# PCB.net
KiCad netlist of a schematic drawn in EAGLE
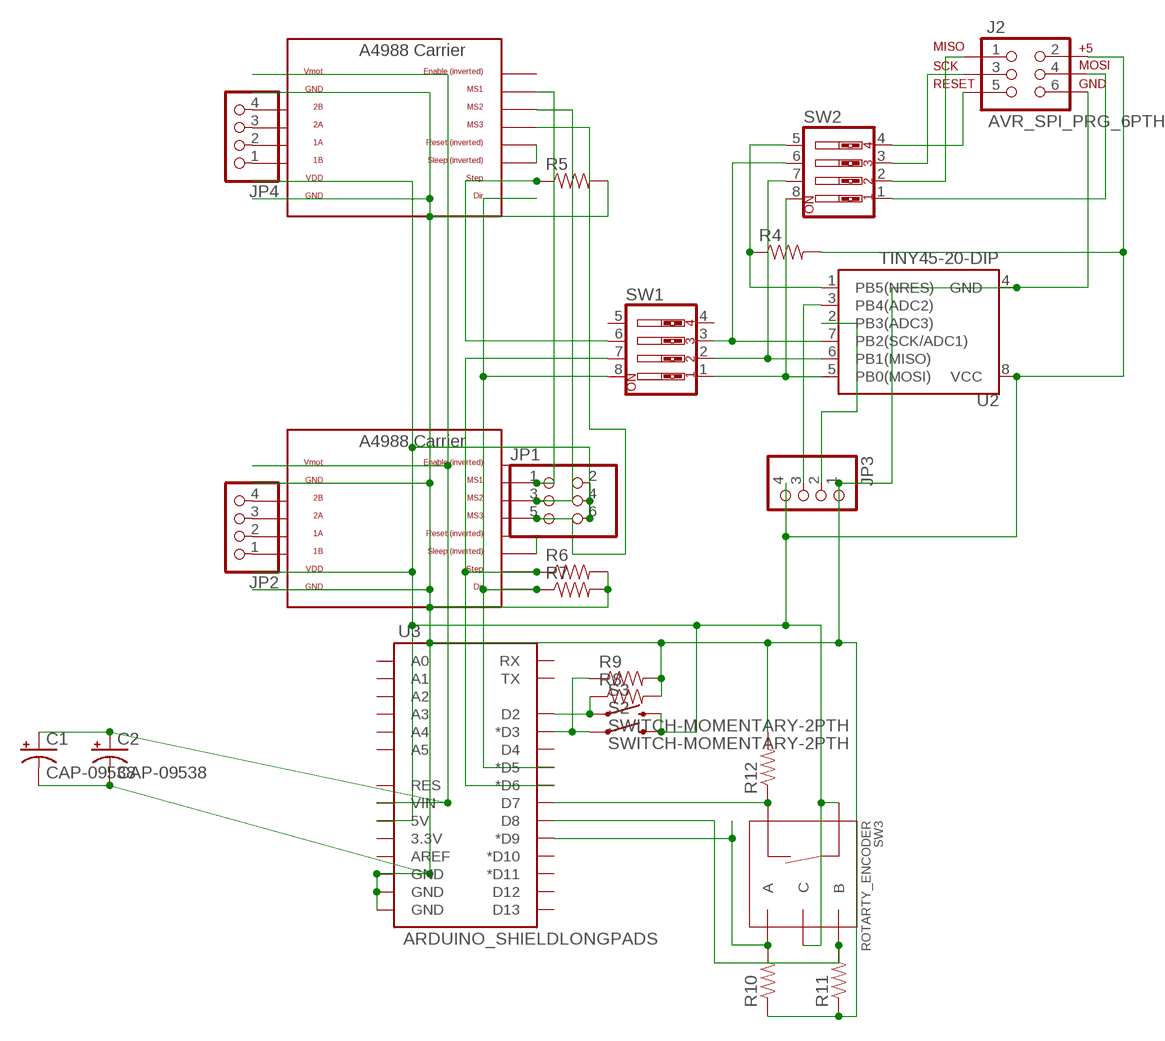
[diagram p0: schematic, sheet 1]

(export (version "E")
  (design (tool "Eeschema 10.0.6"))
  (components
    (comp (ref "C1")
      (value "CAP-09538")
      (footprint "eagle-import:CPOL-RADIAL-1000UF-25V")
      (libsource (lib "eagle-import") (part "1000UF-25V(PTH)"))
    )
    (comp (ref "C2")
      (value "CAP-09538")
      (footprint "eagle-import:CPOL-RADIAL-1000UF-25V")
      (libsource (lib "eagle-import") (part "1000UF-25V(PTH)"))
    )
    (comp (ref "J2")
      (value "AVR_SPI_PRG_6PTH")
      (footprint "eagle-import:2X3")
      (libsource (lib "eagle-import") (part "AVR_SPI_PRG_6PTH"))
    )
    (comp (ref "JP1")
      (value "PINHD-2X3")
      (footprint "eagle-import:2X03")
      (libsource (lib "eagle-import") (part "PINHD-2X3"))
    )
    (comp (ref "JP2")
      (value "PINHD-1X4")
      (footprint "eagle-import:1X04")
      (libsource (lib "eagle-import") (part "PINHD-1X4"))
    )
    (comp (ref "JP3")
      (value "PINHD-1X4")
      (footprint "eagle-import:1X04")
      (libsource (lib "eagle-import") (part "PINHD-1X4"))
    )
    (comp (ref "JP4")
      (value "PINHD-1X4")
      (footprint "eagle-import:1X04")
      (libsource (lib "eagle-import") (part "PINHD-1X4"))
    )
    (comp (ref "R4")
      (value "RESISTOR1206")
      (footprint "eagle-import:1206")
      (libsource (lib "eagle-import") (part "RESISTOR1206"))
    )
    (comp (ref "R5")
      (value "RESISTOR1206")
      (footprint "eagle-import:1206")
      (libsource (lib "eagle-import") (part "RESISTOR1206"))
    )
    (comp (ref "R6")
      (value "RESISTOR1206")
      (footprint "eagle-import:1206")
      (libsource (lib "eagle-import") (part "RESISTOR1206"))
    )
    (comp (ref "R7")
      (value "RESISTOR1206")
      (footprint "eagle-import:1206")
      (libsource (lib "eagle-import") (part "RESISTOR1206"))
    )
    (comp (ref "R8")
      (value "RESISTOR1206")
      (footprint "eagle-import:1206")
      (libsource (lib "eagle-import") (part "RESISTOR1206"))
    )
    (comp (ref "R9")
      (value "RESISTOR1206")
      (footprint "eagle-import:1206")
      (libsource (lib "eagle-import") (part "RESISTOR1206"))
    )
    (comp (ref "R10")
      (value "RESISTOR1206")
      (footprint "eagle-import:1206")
      (libsource (lib "eagle-import") (part "RESISTOR1206"))
    )
    (comp (ref "R11")
      (value "RESISTOR1206")
      (footprint "eagle-import:1206")
      (libsource (lib "eagle-import") (part "RESISTOR1206"))
    )
    (comp (ref "R12")
      (value "RESISTOR1206")
      (footprint "eagle-import:1206")
      (libsource (lib "eagle-import") (part "RESISTOR1206"))
    )
    (comp (ref "S2")
      (value "SWITCH-MOMENTARY-2PTH")
      (footprint "eagle-import:TACTILE-PTH")
      (libsource (lib "eagle-import") (part "SWITCH-MOMENTARY-2PTH"))
    )
    (comp (ref "S3")
      (value "SWITCH-MOMENTARY-2PTH")
      (footprint "eagle-import:TACTILE-PTH")
      (libsource (lib "eagle-import") (part "SWITCH-MOMENTARY-2PTH"))
    )
    (comp (ref "SW1")
      (value "SW_DIP-4")
      (footprint "eagle-import:EDG-04")
      (libsource (lib "eagle-import") (part "SW_DIP-4"))
    )
    (comp (ref "SW2")
      (value "SW_DIP-4")
      (footprint "eagle-import:EDG-04")
      (libsource (lib "eagle-import") (part "SW_DIP-4"))
    )
    (comp (ref "SW3")
      (value "ROTARTY_ENCODER")
      (footprint "eagle-import:ROTARY_ENC_PLAIN")
      (libsource (lib "eagle-import") (part "ROTARTY_ENCODER"))
    )
    (comp (ref "U$3")
      (value "A4988BREAKOUT")
      (footprint "eagle-import:A4988BREAKOUT")
      (libsource (lib "eagle-import") (part "A4988BREAKOUT"))
    )
    (comp (ref "U$4")
      (value "A4988BREAKOUT")
      (footprint "eagle-import:A4988BREAKOUT")
      (libsource (lib "eagle-import") (part "A4988BREAKOUT"))
    )
    (comp (ref "U2")
      (value "TINY45-20-DIP")
      (footprint "eagle-import:DIP08")
      (libsource (lib "eagle-import") (part "ATTINY45TINY45-20-DIP"))
    )
    (comp (ref "U3")
      (value "ARDUINO_SHIELDLONGPADS")
      (footprint "eagle-import:DUEMILANOVE_SHIELD_LONGPADS")
      (libsource (lib "eagle-import") (part "ARDUINO_SHIELDLONGPADS"))
    )
  )
  (nets
    (net (code "1") (name "Net-(C1-Pad+)") (class "Default")
      (node (ref "C1") (pin "+") (pinfunction "+_+") (pintype "passive"))
      (node (ref "C2") (pin "+") (pinfunction "+_+") (pintype "passive"))
      (node (ref "U$3") (pin "VMOT") (pinfunction "VMOT_VMOT") (pintype "power_in"))
      (node (ref "U$4") (pin "VMOT") (pinfunction "VMOT_VMOT") (pintype "power_in"))
      (node (ref "U3") (pin "VIN") (pinfunction "VIN_VIN") (pintype "bidirectional"))
    )
    (net (code "2") (name "Net-(J2-Pad1)") (class "Default")
      (node (ref "J2") (pin "1") (pinfunction "1_1") (pintype "passive"))
      (node (ref "SW2") (pin "2") (pinfunction "2_2") (pintype "passive"))
    )
    (net (code "3") (name "Net-(J2-Pad3)") (class "Default")
      (node (ref "J2") (pin "3") (pinfunction "3_3") (pintype "passive"))
      (node (ref "SW2") (pin "3") (pinfunction "3_3") (pintype "passive"))
    )
    (net (code "4") (name "Net-(J2-Pad4)") (class "Default")
      (node (ref "J2") (pin "4") (pinfunction "4_4") (pintype "passive"))
      (node (ref "SW2") (pin "1") (pinfunction "1_1") (pintype "passive"))
    )
    (net (code "5") (name "Net-(J2-Pad5)") (class "Default")
      (node (ref "J2") (pin "5") (pinfunction "5_5") (pintype "passive"))
      (node (ref "SW2") (pin "4") (pinfunction "4_4") (pintype "passive"))
    )
    (net (code "6") (name "Net-(JP1-Pad1)") (class "Default")
      (node (ref "JP1") (pin "1") (pinfunction "1_1") (pintype "passive"))
      (node (ref "U$3") (pin "MS1") (pinfunction "MS1_MS1") (pintype "input"))
      (node (ref "U$4") (pin "MS1") (pinfunction "MS1_MS1") (pintype "input"))
    )
    (net (code "7") (name "Net-(JP1-Pad3)") (class "Default")
      (node (ref "JP1") (pin "3") (pinfunction "3_3") (pintype "passive"))
      (node (ref "U$3") (pin "MS2") (pinfunction "MS2_MS2") (pintype "input"))
      (node (ref "U$4") (pin "MS2") (pinfunction "MS2_MS2") (pintype "input"))
    )
    (net (code "8") (name "Net-(JP1-Pad5)") (class "Default")
      (node (ref "JP1") (pin "5") (pinfunction "5_5") (pintype "passive"))
      (node (ref "U$3") (pin "MS3") (pinfunction "MS3_MS3") (pintype "input"))
      (node (ref "U$4") (pin "MS3") (pinfunction "MS3_MS3") (pintype "input"))
    )
    (net (code "9") (name "Net-(JP2-Pad1)") (class "Default")
      (node (ref "JP2") (pin "1") (pinfunction "1_1") (pintype "passive"))
      (node (ref "U$3") (pin "1B") (pinfunction "1B_1B") (pintype "output"))
    )
    (net (code "10") (name "Net-(JP2-Pad2)") (class "Default")
      (node (ref "JP2") (pin "2") (pinfunction "2_2") (pintype "passive"))
      (node (ref "U$3") (pin "1A") (pinfunction "1A_1A") (pintype "output"))
    )
    (net (code "11") (name "Net-(JP2-Pad3)") (class "Default")
      (node (ref "JP2") (pin "3") (pinfunction "3_3") (pintype "passive"))
      (node (ref "U$3") (pin "2A") (pinfunction "2A_2A") (pintype "output"))
    )
    (net (code "12") (name "Net-(JP2-Pad4)") (class "Default")
      (node (ref "JP2") (pin "4") (pinfunction "4_4") (pintype "passive"))
      (node (ref "U$3") (pin "2B") (pinfunction "2B_2B") (pintype "output"))
    )
    (net (code "13") (name "Net-(JP4-Pad1)") (class "Default")
      (node (ref "JP4") (pin "1") (pinfunction "1_1") (pintype "passive"))
      (node (ref "U$4") (pin "1B") (pinfunction "1B_1B") (pintype "output"))
    )
    (net (code "14") (name "Net-(JP4-Pad2)") (class "Default")
      (node (ref "JP4") (pin "2") (pinfunction "2_2") (pintype "passive"))
      (node (ref "U$4") (pin "1A") (pinfunction "1A_1A") (pintype "output"))
    )
    (net (code "15") (name "Net-(JP4-Pad3)") (class "Default")
      (node (ref "JP4") (pin "3") (pinfunction "3_3") (pintype "passive"))
      (node (ref "U$4") (pin "2A") (pinfunction "2A_2A") (pintype "output"))
    )
    (net (code "16") (name "Net-(JP4-Pad4)") (class "Default")
      (node (ref "JP4") (pin "4") (pinfunction "4_4") (pintype "passive"))
      (node (ref "U$4") (pin "2B") (pinfunction "2B_2B") (pintype "output"))
    )
    (net (code "17") (name "Net-(R5-Pad1)") (class "Default")
      (node (ref "R5") (pin "1") (pinfunction "1_1") (pintype "passive"))
      (node (ref "SW1") (pin "6") (pinfunction "6_6") (pintype "passive"))
      (node (ref "U$4") (pin "STEP") (pinfunction "STEP_STEP") (pintype "input"))
    )
    (net (code "18") (name "Net-(R8-Pad1)") (class "Default")
      (node (ref "R8") (pin "1") (pinfunction "1_1") (pintype "passive"))
      (node (ref "S3") (pin "1") (pinfunction "1_1") (pintype "passive"))
      (node (ref "U3") (pin "D2") (pinfunction "D2_D2") (pintype "bidirectional"))
    )
    (net (code "19") (name "Net-(R11-Pad2)") (class "Default")
      (node (ref "R11") (pin "2") (pinfunction "2_2") (pintype "passive"))
      (node (ref "SW3") (pin "B") (pinfunction "B_B") (pintype "bidirectional"))
      (node (ref "U3") (pin "D8") (pinfunction "D8_D8") (pintype "bidirectional"))
    )
    (net (code "20") (name "Net-(R12-Pad1)") (class "Default")
      (node (ref "R12") (pin "1") (pinfunction "1_1") (pintype "passive"))
      (node (ref "SW3") (pin "SW-") (pinfunction "SW-_SW-") (pintype "bidirectional"))
      (node (ref "U3") (pin "D7") (pinfunction "D7_D7") (pintype "bidirectional"))
    )
    (net (code "21") (name "Net-(S2-2)") (class "Default")
      (node (ref "J2") (pin "2") (pinfunction "2_2") (pintype "passive"))
      (node (ref "JP1") (pin "2") (pinfunction "2_2") (pintype "passive"))
      (node (ref "JP1") (pin "4") (pinfunction "4_4") (pintype "passive"))
      (node (ref "JP1") (pin "6") (pinfunction "6_6") (pintype "passive"))
      (node (ref "JP3") (pin "4") (pinfunction "4_4") (pintype "passive"))
      (node (ref "R4") (pin "2") (pinfunction "2_2") (pintype "passive"))
      (node (ref "S2") (pin "3") (pinfunction "2_3") (pintype "passive"))
      (node (ref "S3") (pin "3") (pinfunction "2_3") (pintype "passive"))
      (node (ref "SW3") (pin "C") (pinfunction "C_C") (pintype "bidirectional"))
      (node (ref "SW3") (pin "SW+") (pinfunction "SW+_SW+") (pintype "bidirectional"))
      (node (ref "U$3") (pin "VDD") (pinfunction "VDD_VDD") (pintype "power_in"))
      (node (ref "U$4") (pin "VDD") (pinfunction "VDD_VDD") (pintype "power_in"))
      (node (ref "U2") (pin "8") (pinfunction "VCC_8") (pintype "bidirectional"))
      (node (ref "U3") (pin "5V") (pinfunction "5V_5V") (pintype "bidirectional"))
    )
    (net (code "22") (name "Net-(U$3-SLEEP)") (class "Default")
      (node (ref "U$3") (pin "RST") (pinfunction "RST_RST") (pintype "input"))
      (node (ref "U$3") (pin "SLP") (pinfunction "SLEEP_SLP") (pintype "input"))
    )
    (net (code "23") (name "Net-(U$4-SLEEP)") (class "Default")
      (node (ref "U$4") (pin "RST") (pinfunction "RST_RST") (pintype "input"))
      (node (ref "U$4") (pin "SLP") (pinfunction "SLEEP_SLP") (pintype "input"))
    )
    (net (code "24") (name "Net-(U2-GND)") (class "Default")
      (node (ref "C1") (pin "-") (pinfunction "-_-") (pintype "passive"))
      (node (ref "C2") (pin "-") (pinfunction "-_-") (pintype "passive"))
      (node (ref "J2") (pin "6") (pinfunction "6_6") (pintype "passive"))
      (node (ref "JP3") (pin "1") (pinfunction "1_1") (pintype "passive"))
      (node (ref "R10") (pin "1") (pinfunction "1_1") (pintype "passive"))
      (node (ref "R11") (pin "1") (pinfunction "1_1") (pintype "passive"))
      (node (ref "R12") (pin "2") (pinfunction "2_2") (pintype "passive"))
      (node (ref "R5") (pin "2") (pinfunction "2_2") (pintype "passive"))
      (node (ref "R6") (pin "2") (pinfunction "2_2") (pintype "passive"))
      (node (ref "R7") (pin "2") (pinfunction "2_2") (pintype "passive"))
      (node (ref "R8") (pin "2") (pinfunction "2_2") (pintype "passive"))
      (node (ref "R9") (pin "2") (pinfunction "2_2") (pintype "passive"))
      (node (ref "U$3") (pin "GND") (pinfunction "GND_GND") (pintype "power_in"))
      (node (ref "U$3") (pin "GND@0") (pinfunction "GND_GND@0") (pintype "power_in"))
      (node (ref "U$4") (pin "GND") (pinfunction "GND_GND") (pintype "power_in"))
      (node (ref "U$4") (pin "GND@0") (pinfunction "GND_GND@0") (pintype "power_in"))
      (node (ref "U2") (pin "4") (pinfunction "GND_4") (pintype "bidirectional"))
      (node (ref "U3") (pin "GND@0") (pinfunction "GND_GND@0") (pintype "bidirectional"))
      (node (ref "U3") (pin "GND@1") (pinfunction "GND_GND@1") (pintype "bidirectional"))
      (node (ref "U3") (pin "GND@2") (pinfunction "GND_GND@2") (pintype "bidirectional"))
    )
    (net (code "25") (name "Net-(U2-PB0(MOSI))") (class "Default")
      (node (ref "SW1") (pin "1") (pinfunction "1_1") (pintype "passive"))
      (node (ref "SW2") (pin "8") (pinfunction "8_8") (pintype "passive"))
      (node (ref "U2") (pin "5") (pinfunction "PB0(MOSI)_5") (pintype "bidirectional"))
    )
    (net (code "26") (name "Net-(U2-PB1(MISO))") (class "Default")
      (node (ref "SW1") (pin "2") (pinfunction "2_2") (pintype "passive"))
      (node (ref "SW2") (pin "7") (pinfunction "7_7") (pintype "passive"))
      (node (ref "U2") (pin "6") (pinfunction "PB1(MISO)_6") (pintype "bidirectional"))
    )
    (net (code "27") (name "Net-(U2-PB2(SCK{slash}ADC1))") (class "Default")
      (node (ref "SW1") (pin "3") (pinfunction "3_3") (pintype "passive"))
      (node (ref "SW2") (pin "6") (pinfunction "6_6") (pintype "passive"))
      (node (ref "U2") (pin "7") (pinfunction "PB2(SCK/ADC1)_7") (pintype "bidirectional"))
    )
    (net (code "28") (name "Net-(U2-PB3(ADC3))") (class "Default")
      (node (ref "JP3") (pin "2") (pinfunction "2_2") (pintype "passive"))
      (node (ref "U2") (pin "2") (pinfunction "PB3(ADC3)_2") (pintype "bidirectional"))
    )
    (net (code "29") (name "Net-(U2-PB4(ADC2))") (class "Default")
      (node (ref "JP3") (pin "3") (pinfunction "3_3") (pintype "passive"))
      (node (ref "U2") (pin "3") (pinfunction "PB4(ADC2)_3") (pintype "bidirectional"))
    )
    (net (code "30") (name "Net-(U2-PB5(NRES))") (class "Default")
      (node (ref "R4") (pin "1") (pinfunction "1_1") (pintype "passive"))
      (node (ref "SW2") (pin "5") (pinfunction "5_5") (pintype "passive"))
      (node (ref "U2") (pin "1") (pinfunction "PB5(NRES)_1") (pintype "bidirectional"))
    )
    (net (code "31") (name "Net-(U3-*D3)") (class "Default")
      (node (ref "R9") (pin "1") (pinfunction "1_1") (pintype "passive"))
      (node (ref "S2") (pin "1") (pinfunction "1_1") (pintype "passive"))
      (node (ref "U3") (pin "D3") (pinfunction "*D3_D3") (pintype "bidirectional"))
    )
    (net (code "32") (name "Net-(U3-*D5)") (class "Default")
      (node (ref "R7") (pin "1") (pinfunction "1_1") (pintype "passive"))
      (node (ref "SW1") (pin "8") (pinfunction "8_8") (pintype "passive"))
      (node (ref "U$3") (pin "DIR") (pinfunction "DIR_DIR") (pintype "input"))
      (node (ref "U$4") (pin "DIR") (pinfunction "DIR_DIR") (pintype "input"))
      (node (ref "U3") (pin "D5") (pinfunction "*D5_D5") (pintype "bidirectional"))
    )
    (net (code "33") (name "Net-(U3-*D6)") (class "Default")
      (node (ref "R6") (pin "1") (pinfunction "1_1") (pintype "passive"))
      (node (ref "SW1") (pin "7") (pinfunction "7_7") (pintype "passive"))
      (node (ref "U$3") (pin "STEP") (pinfunction "STEP_STEP") (pintype "input"))
      (node (ref "U3") (pin "D6") (pinfunction "*D6_D6") (pintype "bidirectional"))
    )
    (net (code "34") (name "Net-(U3-*D9)") (class "Default")
      (node (ref "R10") (pin "2") (pinfunction "2_2") (pintype "passive"))
      (node (ref "SW3") (pin "A") (pinfunction "A_A") (pintype "bidirectional"))
      (node (ref "U3") (pin "D9") (pinfunction "*D9_D9") (pintype "bidirectional"))
    )
    (net (code "35") (name "unconnected-(SW1-Pad4)") (class "Default")
      (node (ref "SW1") (pin "4") (pinfunction "4_4") (pintype "passive"))
    )
    (net (code "36") (name "unconnected-(SW1-Pad5)") (class "Default")
      (node (ref "SW1") (pin "5") (pinfunction "5_5") (pintype "passive"))
    )
    (net (code "37") (name "unconnected-(U$3-PadEN)") (class "Default")
      (node (ref "U$3") (pin "EN") (pinfunction "EN_EN") (pintype "input"))
    )
    (net (code "38") (name "unconnected-(U$4-PadEN)") (class "Default")
      (node (ref "U$4") (pin "EN") (pinfunction "EN_EN") (pintype "input"))
    )
    (net (code "39") (name "unconnected-(U3-*D10-PadD10)") (class "Default")
      (node (ref "U3") (pin "D10") (pinfunction "*D10_D10") (pintype "bidirectional"))
    )
    (net (code "40") (name "unconnected-(U3-*D11-PadD11)") (class "Default")
      (node (ref "U3") (pin "D11") (pinfunction "*D11_D11") (pintype "bidirectional"))
    )
    (net (code "41") (name "unconnected-(U3-Pad3.3V)") (class "Default")
      (node (ref "U3") (pin "3.3V") (pinfunction "3.3V_3.3V") (pintype "bidirectional"))
    )
    (net (code "42") (name "unconnected-(U3-PadA0)") (class "Default")
      (node (ref "U3") (pin "A0") (pinfunction "A0_A0") (pintype "bidirectional"))
    )
    (net (code "43") (name "unconnected-(U3-PadA1)") (class "Default")
      (node (ref "U3") (pin "A1") (pinfunction "A1_A1") (pintype "bidirectional"))
    )
    (net (code "44") (name "unconnected-(U3-PadA2)") (class "Default")
      (node (ref "U3") (pin "A2") (pinfunction "A2_A2") (pintype "bidirectional"))
    )
    (net (code "45") (name "unconnected-(U3-PadA3)") (class "Default")
      (node (ref "U3") (pin "A3") (pinfunction "A3_A3") (pintype "bidirectional"))
    )
    (net (code "46") (name "unconnected-(U3-PadA4)") (class "Default")
      (node (ref "U3") (pin "A4") (pinfunction "A4_A4") (pintype "bidirectional"))
    )
    (net (code "47") (name "unconnected-(U3-PadA5)") (class "Default")
      (node (ref "U3") (pin "A5") (pinfunction "A5_A5") (pintype "bidirectional"))
    )
    (net (code "48") (name "unconnected-(U3-PadAREF)") (class "Default")
      (node (ref "U3") (pin "AREF") (pinfunction "AREF_AREF") (pintype "bidirectional"))
    )
    (net (code "49") (name "unconnected-(U3-PadD4)") (class "Default")
      (node (ref "U3") (pin "D4") (pinfunction "D4_D4") (pintype "bidirectional"))
    )
    (net (code "50") (name "unconnected-(U3-PadD12)") (class "Default")
      (node (ref "U3") (pin "D12") (pinfunction "D12_D12") (pintype "bidirectional"))
    )
    (net (code "51") (name "unconnected-(U3-PadD13)") (class "Default")
      (node (ref "U3") (pin "D13") (pinfunction "D13_D13") (pintype "bidirectional"))
    )
    (net (code "52") (name "unconnected-(U3-PadRES)") (class "Default")
      (node (ref "U3") (pin "RES") (pinfunction "RES_RES") (pintype "bidirectional"))
    )
    (net (code "53") (name "unconnected-(U3-PadRX)") (class "Default")
      (node (ref "U3") (pin "RX") (pinfunction "RX_RX") (pintype "bidirectional"))
    )
    (net (code "54") (name "unconnected-(U3-PadTX)") (class "Default")
      (node (ref "U3") (pin "TX") (pinfunction "TX_TX") (pintype "bidirectional"))
    )
  )
)
